# shield_v2_0.net
KiCad netlist of a schematic drawn in EAGLE
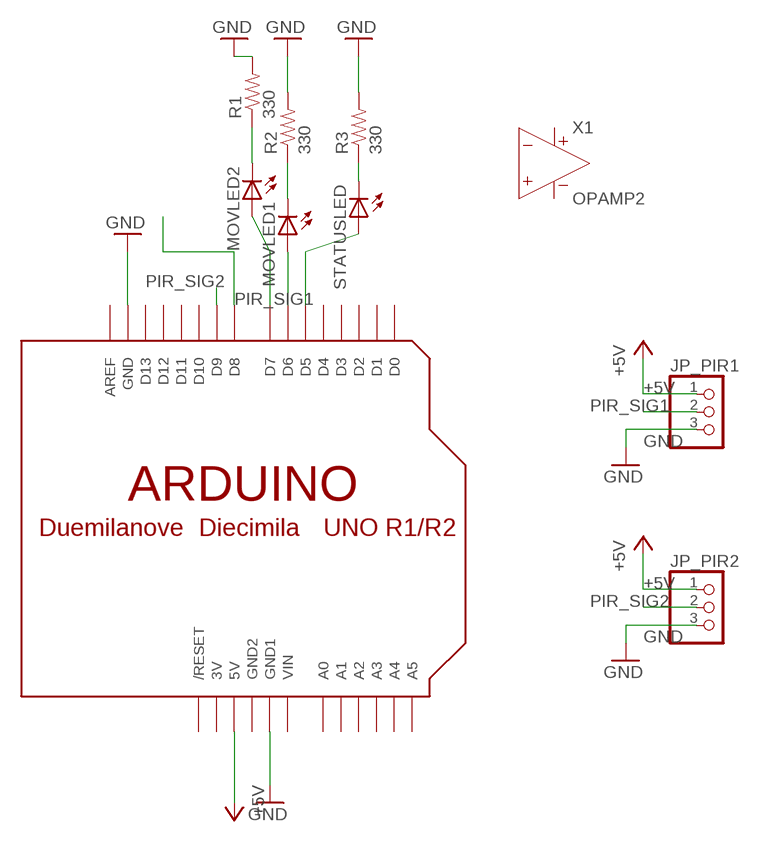
[diagram p0: schematic, sheet 1]

(export (version "E")
  (design (tool "Eeschema 10.0.6"))
  (components
    (comp (ref "JP_PIR1")
      (value "PINHD-1X3")
      (footprint "eagle-import:1X03")
      (libsource (lib "eagle-import") (part "PINHD-1X3"))
    )
    (comp (ref "JP_PIR2")
      (value "PINHD-1X3")
      (footprint "eagle-import:1X03")
      (libsource (lib "eagle-import") (part "PINHD-1X3"))
    )
    (comp (ref "MOVLED1")
      (value "LED5MM")
      (footprint "eagle-import:LED5MM")
      (libsource (lib "eagle-import") (part "LED5MM"))
    )
    (comp (ref "MOVLED2")
      (value "LED5MM")
      (footprint "eagle-import:LED5MM")
      (libsource (lib "eagle-import") (part "LED5MM"))
    )
    (comp (ref "R1")
      (value "330")
      (footprint "eagle-import:AXIAL-0.4")
      (libsource (lib "eagle-import") (part "RESISTORPTH-1/4W"))
    )
    (comp (ref "R2")
      (value "330")
      (footprint "eagle-import:AXIAL-0.4")
      (libsource (lib "eagle-import") (part "RESISTORPTH-1/4W"))
    )
    (comp (ref "R3")
      (value "330")
      (footprint "eagle-import:AXIAL-0.4")
      (libsource (lib "eagle-import") (part "RESISTORPTH-1/4W"))
    )
    (comp (ref "STATUSLED")
      (value "LED5MM")
      (footprint "eagle-import:LED5MM")
      (libsource (lib "eagle-import") (part "LED5MM"))
    )
    (comp (ref "U$1")
      (value "ARDUINOUNO")
      (footprint "eagle-import:ARDUINO")
      (libsource (lib "eagle-import") (part "ARDUINOUNO"))
    )
    (comp (ref "X1")
      (value "OPAMP2")
      (footprint "eagle-import:S8")
      (libsource (lib "eagle-import") (part "OPAMP2"))
    )
  )
  (nets
    (net (code "1") (name "+5V") (class "Default")
      (node (ref "JP_PIR1") (pin "1") (pinfunction "1_1") (pintype "passive"))
      (node (ref "JP_PIR2") (pin "1") (pinfunction "1_1") (pintype "passive"))
      (node (ref "U$1") (pin "5V") (pinfunction "5V_5V") (pintype "power_in"))
    )
    (net (code "2") (name "/3V") (class "Default")
      (node (ref "U$1") (pin "3V") (pinfunction "3V_3V") (pintype "power_in"))
    )
    (net (code "3") (name "/GND2") (class "Default")
      (node (ref "U$1") (pin "GND2") (pinfunction "GND2_GND2") (pintype "power_in"))
    )
    (net (code "4") (name "/PIR_SIG1") (class "Default")
      (node (ref "JP_PIR1") (pin "2") (pinfunction "2_2") (pintype "passive"))
      (node (ref "U$1") (pin "D8") (pinfunction "D8_D8") (pintype "bidirectional"))
    )
    (net (code "5") (name "/PIR_SIG2") (class "Default")
      (node (ref "JP_PIR2") (pin "2") (pinfunction "2_2") (pintype "passive"))
      (node (ref "U$1") (pin "D9") (pinfunction "D9_D9") (pintype "bidirectional"))
    )
    (net (code "6") (name "/VIN") (class "Default")
      (node (ref "U$1") (pin "VIN") (pinfunction "VIN_VIN") (pintype "power_in"))
    )
    (net (code "7") (name "GND") (class "Default")
      (node (ref "JP_PIR1") (pin "3") (pinfunction "3_3") (pintype "passive"))
      (node (ref "JP_PIR2") (pin "3") (pinfunction "3_3") (pintype "passive"))
      (node (ref "R1") (pin "P$2") (pinfunction "2_P$2") (pintype "passive"))
      (node (ref "R2") (pin "P$2") (pinfunction "2_P$2") (pintype "passive"))
      (node (ref "R3") (pin "P$2") (pinfunction "2_P$2") (pintype "passive"))
      (node (ref "U$1") (pin "GND") (pinfunction "GND_GND") (pintype "power_in"))
      (node (ref "U$1") (pin "GND1") (pinfunction "GND1_GND1") (pintype "power_in"))
    )
    (net (code "8") (name "Net-(MOVLED1-C)") (class "Default")
      (node (ref "MOVLED1") (pin "K") (pinfunction "C_K") (pintype "passive"))
      (node (ref "R2") (pin "P$1") (pinfunction "1_P$1") (pintype "passive"))
    )
    (net (code "9") (name "Net-(MOVLED1-PadA)") (class "Default")
      (node (ref "MOVLED1") (pin "A") (pinfunction "A_A") (pintype "passive"))
      (node (ref "U$1") (pin "D6") (pinfunction "D6_D6") (pintype "bidirectional"))
    )
    (net (code "10") (name "Net-(MOVLED2-C)") (class "Default")
      (node (ref "MOVLED2") (pin "K") (pinfunction "C_K") (pintype "passive"))
      (node (ref "R1") (pin "P$1") (pinfunction "1_P$1") (pintype "passive"))
    )
    (net (code "11") (name "Net-(MOVLED2-PadA)") (class "Default")
      (node (ref "MOVLED2") (pin "A") (pinfunction "A_A") (pintype "passive"))
      (node (ref "U$1") (pin "D7") (pinfunction "D7_D7") (pintype "bidirectional"))
    )
    (net (code "12") (name "Net-(R3-1)") (class "Default")
      (node (ref "R3") (pin "P$1") (pinfunction "1_P$1") (pintype "passive"))
      (node (ref "STATUSLED") (pin "K") (pinfunction "C_K") (pintype "passive"))
    )
    (net (code "13") (name "Net-(STATUSLED-PadA)") (class "Default")
      (node (ref "STATUSLED") (pin "A") (pinfunction "A_A") (pintype "passive"))
      (node (ref "U$1") (pin "D5") (pinfunction "D5_D5") (pintype "bidirectional"))
    )
    (net (code "14") (name "unconnected-(U$1-PadA0)") (class "Default")
      (node (ref "U$1") (pin "A0") (pinfunction "A0_A0") (pintype "bidirectional"))
    )
    (net (code "15") (name "unconnected-(U$1-PadA1)") (class "Default")
      (node (ref "U$1") (pin "A1") (pinfunction "A1_A1") (pintype "bidirectional"))
    )
    (net (code "16") (name "unconnected-(U$1-PadA2)") (class "Default")
      (node (ref "U$1") (pin "A2") (pinfunction "A2_A2") (pintype "bidirectional"))
    )
    (net (code "17") (name "unconnected-(U$1-PadA3)") (class "Default")
      (node (ref "U$1") (pin "A3") (pinfunction "A3_A3") (pintype "bidirectional"))
    )
    (net (code "18") (name "unconnected-(U$1-PadA4)") (class "Default")
      (node (ref "U$1") (pin "A4") (pinfunction "A4_A4") (pintype "bidirectional"))
    )
    (net (code "19") (name "unconnected-(U$1-PadA5)") (class "Default")
      (node (ref "U$1") (pin "A5") (pinfunction "A5_A5") (pintype "bidirectional"))
    )
    (net (code "20") (name "unconnected-(U$1-PadAREF)") (class "Default")
      (node (ref "U$1") (pin "AREF") (pinfunction "AREF_AREF") (pintype "bidirectional"))
    )
    (net (code "21") (name "unconnected-(U$1-PadD0)") (class "Default")
      (node (ref "U$1") (pin "D0") (pinfunction "D0_D0") (pintype "bidirectional"))
    )
    (net (code "22") (name "unconnected-(U$1-PadD1)") (class "Default")
      (node (ref "U$1") (pin "D1") (pinfunction "D1_D1") (pintype "bidirectional"))
    )
    (net (code "23") (name "unconnected-(U$1-PadD2)") (class "Default")
      (node (ref "U$1") (pin "D2") (pinfunction "D2_D2") (pintype "bidirectional"))
    )
    (net (code "24") (name "unconnected-(U$1-PadD3)") (class "Default")
      (node (ref "U$1") (pin "D3") (pinfunction "D3_D3") (pintype "bidirectional"))
    )
    (net (code "25") (name "unconnected-(U$1-PadD4)") (class "Default")
      (node (ref "U$1") (pin "D4") (pinfunction "D4_D4") (pintype "bidirectional"))
    )
    (net (code "26") (name "unconnected-(U$1-PadD10)") (class "Default")
      (node (ref "U$1") (pin "D10") (pinfunction "D10_D10") (pintype "bidirectional"))
    )
    (net (code "27") (name "unconnected-(U$1-PadD11)") (class "Default")
      (node (ref "U$1") (pin "D11") (pinfunction "D11_D11") (pintype "bidirectional"))
    )
    (net (code "28") (name "unconnected-(U$1-PadD12)") (class "Default")
      (node (ref "U$1") (pin "D12") (pinfunction "D12_D12") (pintype "bidirectional"))
    )
    (net (code "29") (name "unconnected-(U$1-PadD13)") (class "Default")
      (node (ref "U$1") (pin "D13") (pinfunction "D13_D13") (pintype "bidirectional"))
    )
    (net (code "30") (name "unconnected-(U$1-{slash}RESET-PadRESET)") (class "Default")
      (node (ref "U$1") (pin "RESET") (pinfunction "/RESET_RESET") (pintype "bidirectional"))
    )
    (net (code "31") (name "unconnected-(X1-IN+-Pad1)") (class "Default")
      (node (ref "X1") (pin "1") (pinfunction "IN+_1") (pintype "passive"))
    )
    (net (code "32") (name "unconnected-(X1-IN--Pad2)") (class "Default")
      (node (ref "X1") (pin "2") (pinfunction "IN-_2") (pintype "passive"))
    )
    (net (code "33") (name "unconnected-(X1-OUT-Pad3)") (class "Default")
      (node (ref "X1") (pin "3") (pinfunction "OUT_3") (pintype "passive"))
    )
    (net (code "34") (name "unconnected-(X1-V+-Pad8)") (class "Default")
      (node (ref "X1") (pin "8") (pinfunction "V+_8") (pintype "passive"))
    )
    (net (code "35") (name "unconnected-(X1-V--Pad4)") (class "Default")
      (node (ref "X1") (pin "4") (pinfunction "V-_4") (pintype "passive"))
    )
  )
)
